# PlacaDeDezvoltareGenerala.net
KiCad netlist of a schematic drawn in Altium Designer
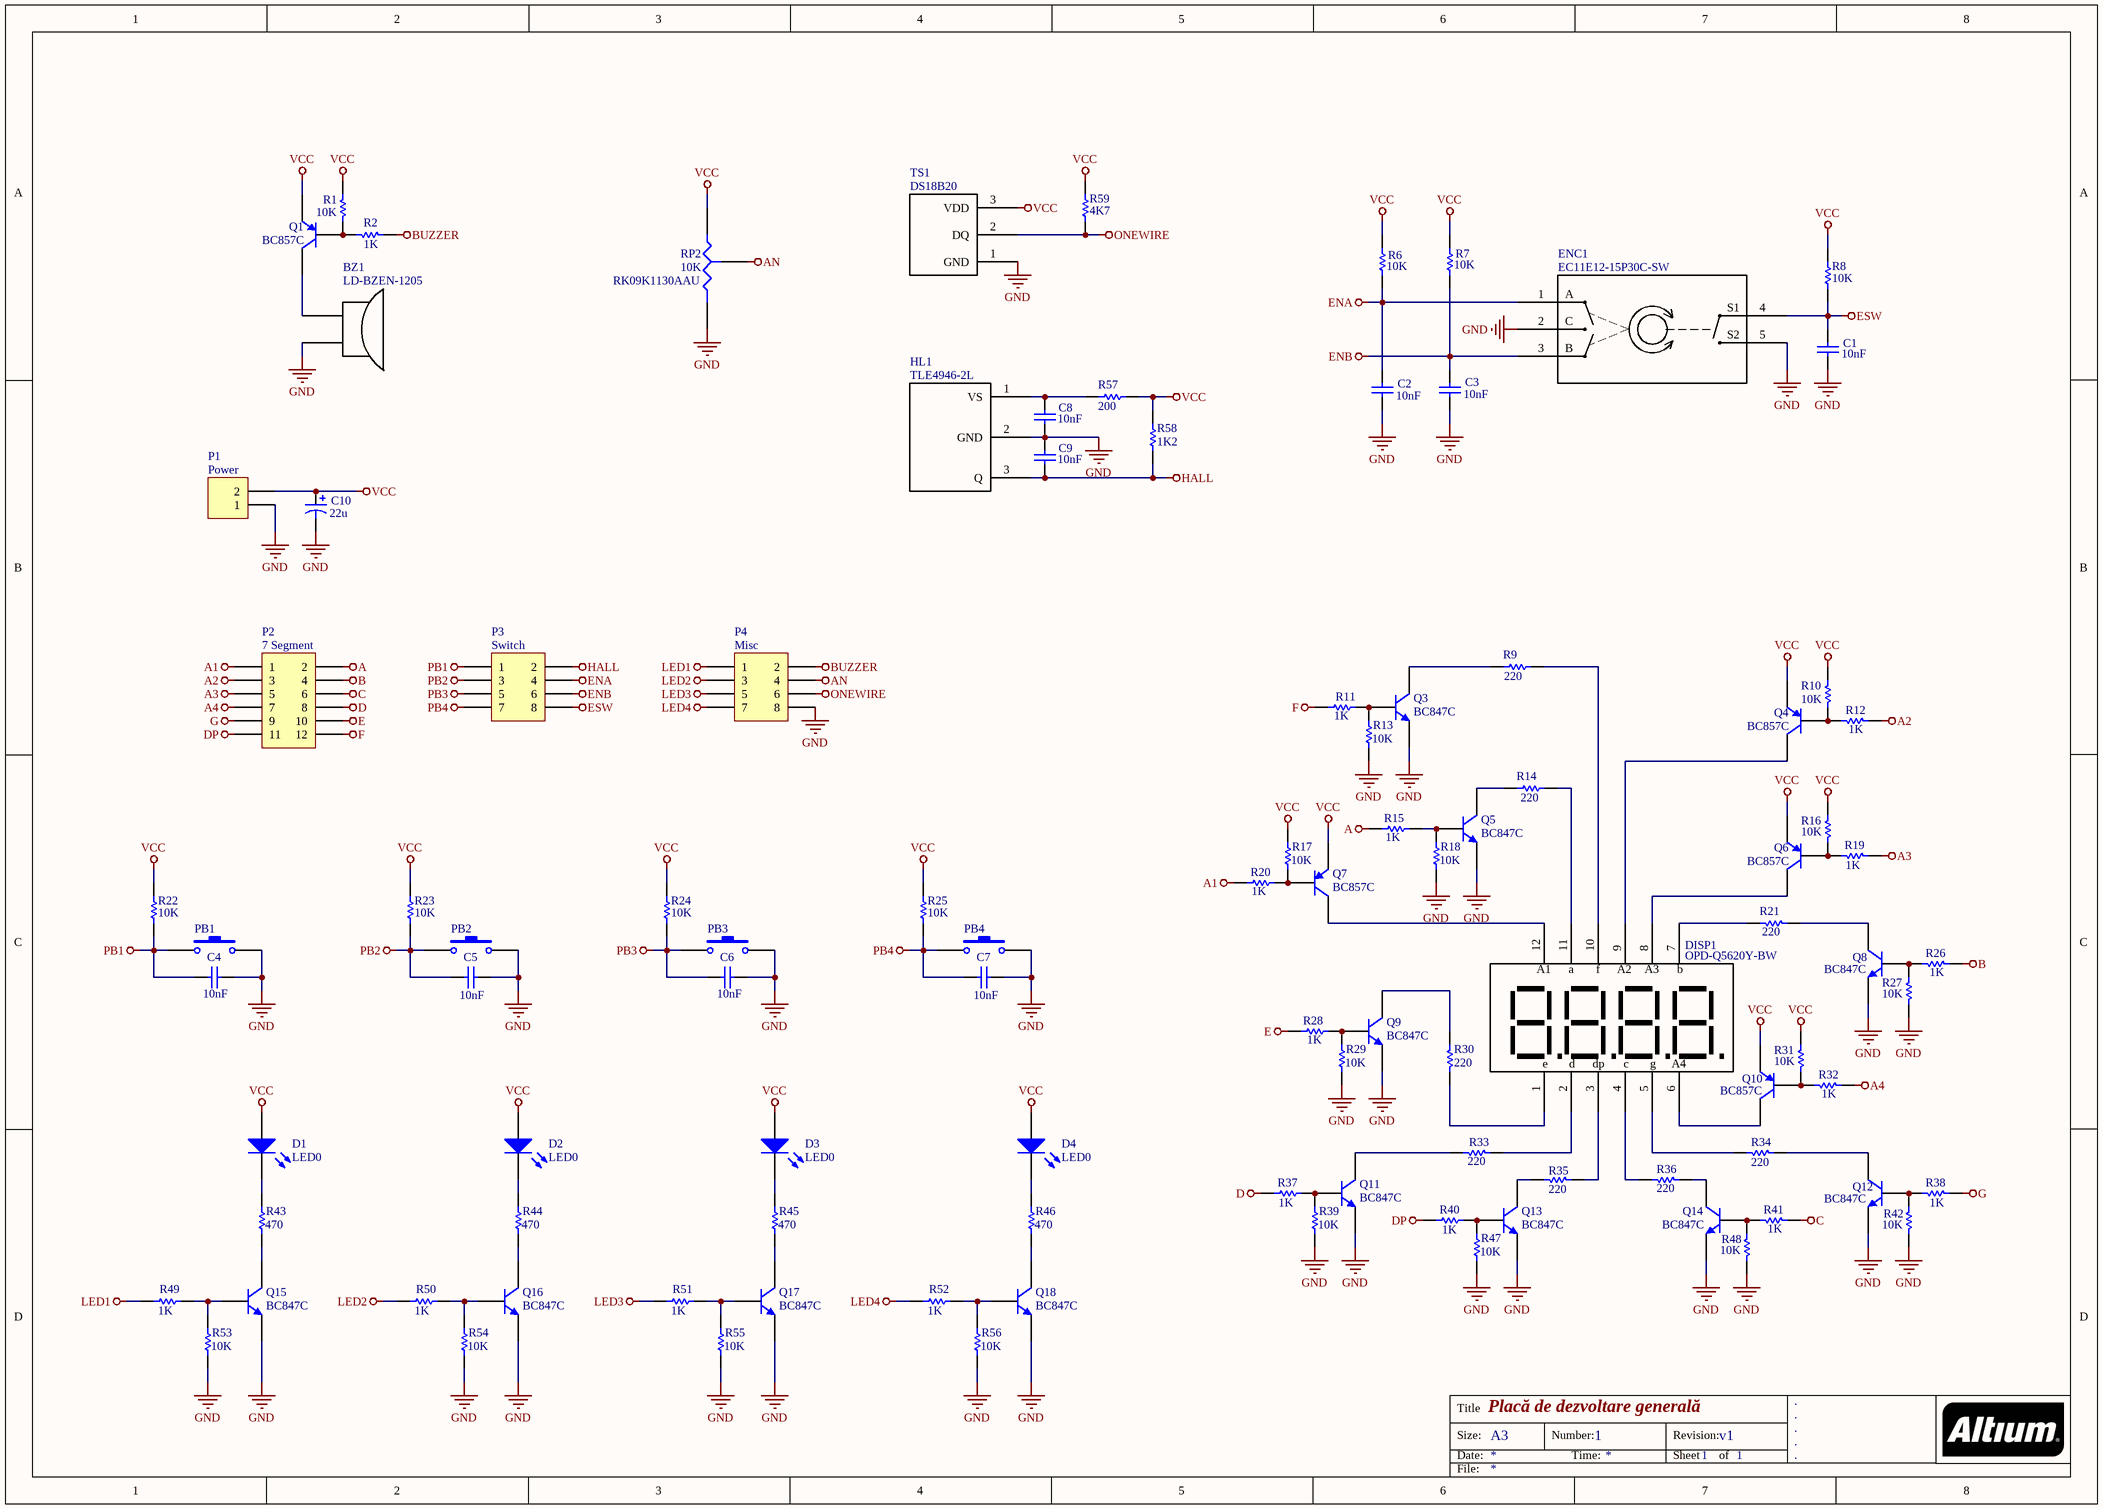
[diagram p0: PlacaDeDezvoltareGenerala.SchDoc]

(export (version "E")
  (design (tool "Eeschema 10.0.6"))
  (components
    (comp (ref "BZ1")
      (value "LD-BZEN-1205")
      (footprint "BUZZER_12.0X8.5MM")
      (libsource (lib "PlacaDeDezvoltareGenerala") (part "Buzzer"))
    )
    (comp (ref "C1")
      (value "10nF")
      (footprint "CAP 0805")
      (description "Capacitor")
      (fields (field (name "Comment") "Cap") (field (name "PUBLISHER") "Altium Limited"))
      (libsource (lib "Miscellaneous Devices") (part "Cap"))
    )
    (comp (ref "C2")
      (value "10nF")
      (footprint "CAP 0805")
      (description "Capacitor")
      (fields (field (name "Comment") "Cap") (field (name "PUBLISHER") "Altium Limited"))
      (libsource (lib "Miscellaneous Devices") (part "Cap"))
    )
    (comp (ref "C3")
      (value "10nF")
      (footprint "CAP 0805")
      (description "Capacitor")
      (fields (field (name "Comment") "Cap") (field (name "PUBLISHER") "Altium Limited"))
      (libsource (lib "Miscellaneous Devices") (part "Cap"))
    )
    (comp (ref "C4")
      (value "10nF")
      (footprint "CAP 0805")
      (description "Capacitor")
      (fields (field (name "Comment") "Cap") (field (name "PUBLISHER") "Altium Limited"))
      (libsource (lib "Miscellaneous Devices") (part "Cap"))
    )
    (comp (ref "C5")
      (value "10nF")
      (footprint "CAP 0805")
      (description "Capacitor")
      (fields (field (name "Comment") "Cap") (field (name "PUBLISHER") "Altium Limited"))
      (libsource (lib "Miscellaneous Devices") (part "Cap"))
    )
    (comp (ref "C6")
      (value "10nF")
      (footprint "CAP 0805")
      (description "Capacitor")
      (fields (field (name "Comment") "Cap") (field (name "PUBLISHER") "Altium Limited"))
      (libsource (lib "Miscellaneous Devices") (part "Cap"))
    )
    (comp (ref "C7")
      (value "10nF")
      (footprint "CAP 0805")
      (description "Capacitor")
      (fields (field (name "Comment") "Cap") (field (name "PUBLISHER") "Altium Limited"))
      (libsource (lib "Miscellaneous Devices") (part "Cap"))
    )
    (comp (ref "C8")
      (value "10nF")
      (footprint "CAP 0805")
      (description "Capacitor")
      (fields (field (name "Comment") "Cap") (field (name "PUBLISHER") "Altium Limited"))
      (libsource (lib "Miscellaneous Devices") (part "Cap"))
    )
    (comp (ref "C9")
      (value "10nF")
      (footprint "CAP 0805")
      (description "Capacitor")
      (fields (field (name "Comment") "Cap") (field (name "PUBLISHER") "Altium Limited"))
      (libsource (lib "Miscellaneous Devices") (part "Cap"))
    )
    (comp (ref "C10")
      (value "22u")
      (footprint "CAP_ELEC_6.3x4.2")
      (description "Polarized Capacitor (Radial)")
      (fields (field (name "Comment") "Cap Pol1") (field (name "PUBLISHER") "Altium Limited"))
      (libsource (lib "Miscellaneous Devices") (part "Cap Pol1"))
    )
    (comp (ref "D1")
      (value "LED0")
      (footprint "LED0603GR")
      (description "Typical INFRARED GaAs LED")
      (fields (field (name "PUBLISHER") "Altium Limited"))
      (libsource (lib "Miscellaneous Devices") (part "LED0"))
    )
    (comp (ref "D2")
      (value "LED0")
      (footprint "LED0603GR")
      (description "Typical INFRARED GaAs LED")
      (fields (field (name "PUBLISHER") "Altium Limited"))
      (libsource (lib "Miscellaneous Devices") (part "LED0"))
    )
    (comp (ref "D3")
      (value "LED0")
      (footprint "LED0603GR")
      (description "Typical INFRARED GaAs LED")
      (fields (field (name "PUBLISHER") "Altium Limited"))
      (libsource (lib "Miscellaneous Devices") (part "LED0"))
    )
    (comp (ref "D4")
      (value "LED0")
      (footprint "LED0603GR")
      (description "Typical INFRARED GaAs LED")
      (fields (field (name "PUBLISHER") "Altium Limited"))
      (libsource (lib "Miscellaneous Devices") (part "LED0"))
    )
    (comp (ref "DISP1")
      (value "OPD-Q5620Y-BW")
      (footprint "7-SEG")
      (libsource (lib "PlacaDeDezvoltareGenerala") (part "7 Segment"))
    )
    (comp (ref "ENC1")
      (value "EC11E12-15P30C-SW")
      (footprint "EC11E12")
      (libsource (lib "PlacaDeDezvoltareGenerala") (part "Encoder"))
    )
    (comp (ref "HL1")
      (value "TLE4946-2L")
      (footprint "TLE4946-2L")
      (libsource (lib "PlacaDeDezvoltareGenerala") (part "Hall Latch TLE4946-2L"))
    )
    (comp (ref "P1")
      (value "Power")
      (footprint "HEADER_1x2_2.54")
      (description "Header, 2-Pin")
      (fields (field (name "PUBLISHER") "Altium Limited"))
      (libsource (lib "Miscellaneous Connectors") (part "Header 2"))
    )
    (comp (ref "P2")
      (value "7 Segment")
      (footprint "HEADER_2x6_2.54")
      (description "Header, 6-Pin, Dual row")
      (fields (field (name "PUBLISHER") "Altium Limited"))
      (libsource (lib "Miscellaneous Connectors") (part "Header 6X2"))
    )
    (comp (ref "P3")
      (value "Switch")
      (footprint "HEADER_2x4_2.54")
      (description "Header, 4-Pin, Dual row, Right Angle")
      (fields (field (name "PUBLISHER") "Altium Limited"))
      (libsource (lib "Miscellaneous Connectors") (part "Header 4X2H"))
    )
    (comp (ref "P4")
      (value "Misc")
      (footprint "HEADER_2x4_2.54")
      (description "Header, 4-Pin, Dual row, Right Angle")
      (fields (field (name "PUBLISHER") "Altium Limited"))
      (libsource (lib "Miscellaneous Connectors") (part "Header 4X2H"))
    )
    (comp (ref "PB1")
      (value "SW-PB")
      (footprint "PUSH BUTTON")
      (description "Switch")
      (fields (field (name "PUBLISHER") "Altium Limited"))
      (libsource (lib "Miscellaneous Devices") (part "SW-PB"))
    )
    (comp (ref "PB2")
      (value "SW-PB")
      (footprint "PUSH BUTTON")
      (description "Switch")
      (fields (field (name "PUBLISHER") "Altium Limited"))
      (libsource (lib "Miscellaneous Devices") (part "SW-PB"))
    )
    (comp (ref "PB3")
      (value "SW-PB")
      (footprint "PUSH BUTTON")
      (description "Switch")
      (fields (field (name "PUBLISHER") "Altium Limited"))
      (libsource (lib "Miscellaneous Devices") (part "SW-PB"))
    )
    (comp (ref "PB4")
      (value "SW-PB")
      (footprint "PUSH BUTTON")
      (description "Switch")
      (fields (field (name "PUBLISHER") "Altium Limited"))
      (libsource (lib "Miscellaneous Devices") (part "SW-PB"))
    )
    (comp (ref "Q1")
      (value "BC857C")
      (footprint "BC847C/BC857C")
      (description "PNP General Purpose Amplifier")
      (fields (field (name "PUBLISHER") "Altium Limited"))
      (libsource (lib "Miscellaneous Devices") (part "2N3906"))
    )
    (comp (ref "Q3")
      (value "BC847C")
      (footprint "BC847C/BC857C")
      (description "NPN General Purpose Amplifier")
      (fields (field (name "PUBLISHER") "Altium Limited"))
      (libsource (lib "Miscellaneous Devices") (part "2N3904"))
    )
    (comp (ref "Q4")
      (value "BC857C")
      (footprint "BC847C/BC857C")
      (description "PNP General Purpose Amplifier")
      (fields (field (name "PUBLISHER") "Altium Limited"))
      (libsource (lib "Miscellaneous Devices") (part "2N3906"))
    )
    (comp (ref "Q5")
      (value "BC847C")
      (footprint "BC847C/BC857C")
      (description "NPN General Purpose Amplifier")
      (fields (field (name "PUBLISHER") "Altium Limited"))
      (libsource (lib "Miscellaneous Devices") (part "2N3904"))
    )
    (comp (ref "Q6")
      (value "BC857C")
      (footprint "BC847C/BC857C")
      (description "PNP General Purpose Amplifier")
      (fields (field (name "PUBLISHER") "Altium Limited"))
      (libsource (lib "Miscellaneous Devices") (part "2N3906"))
    )
    (comp (ref "Q7")
      (value "BC857C")
      (footprint "BC847C/BC857C")
      (description "PNP General Purpose Amplifier")
      (fields (field (name "PUBLISHER") "Altium Limited"))
      (libsource (lib "Miscellaneous Devices") (part "2N3906"))
    )
    (comp (ref "Q8")
      (value "BC847C")
      (footprint "BC847C/BC857C")
      (description "NPN General Purpose Amplifier")
      (fields (field (name "PUBLISHER") "Altium Limited"))
      (libsource (lib "Miscellaneous Devices") (part "2N3904"))
    )
    (comp (ref "Q9")
      (value "BC847C")
      (footprint "BC847C/BC857C")
      (description "NPN General Purpose Amplifier")
      (fields (field (name "PUBLISHER") "Altium Limited"))
      (libsource (lib "Miscellaneous Devices") (part "2N3904"))
    )
    (comp (ref "Q10")
      (value "BC857C")
      (footprint "BC847C/BC857C")
      (description "PNP General Purpose Amplifier")
      (fields (field (name "PUBLISHER") "Altium Limited"))
      (libsource (lib "Miscellaneous Devices") (part "2N3906"))
    )
    (comp (ref "Q11")
      (value "BC847C")
      (footprint "BC847C/BC857C")
      (description "NPN General Purpose Amplifier")
      (fields (field (name "PUBLISHER") "Altium Limited"))
      (libsource (lib "Miscellaneous Devices") (part "2N3904"))
    )
    (comp (ref "Q12")
      (value "BC847C")
      (footprint "BC847C/BC857C")
      (description "NPN General Purpose Amplifier")
      (fields (field (name "PUBLISHER") "Altium Limited"))
      (libsource (lib "Miscellaneous Devices") (part "2N3904"))
    )
    (comp (ref "Q13")
      (value "BC847C")
      (footprint "BC847C/BC857C")
      (description "NPN General Purpose Amplifier")
      (fields (field (name "PUBLISHER") "Altium Limited"))
      (libsource (lib "Miscellaneous Devices") (part "2N3904"))
    )
    (comp (ref "Q14")
      (value "BC847C")
      (footprint "BC847C/BC857C")
      (description "NPN General Purpose Amplifier")
      (fields (field (name "PUBLISHER") "Altium Limited"))
      (libsource (lib "Miscellaneous Devices") (part "2N3904"))
    )
    (comp (ref "Q15")
      (value "BC847C")
      (footprint "BC847C/BC857C")
      (description "NPN General Purpose Amplifier")
      (fields (field (name "PUBLISHER") "Altium Limited"))
      (libsource (lib "Miscellaneous Devices") (part "2N3904"))
    )
    (comp (ref "Q16")
      (value "BC847C")
      (footprint "BC847C/BC857C")
      (description "NPN General Purpose Amplifier")
      (fields (field (name "PUBLISHER") "Altium Limited"))
      (libsource (lib "Miscellaneous Devices") (part "2N3904"))
    )
    (comp (ref "Q17")
      (value "BC847C")
      (footprint "BC847C/BC857C")
      (description "NPN General Purpose Amplifier")
      (fields (field (name "PUBLISHER") "Altium Limited"))
      (libsource (lib "Miscellaneous Devices") (part "2N3904"))
    )
    (comp (ref "Q18")
      (value "BC847C")
      (footprint "BC847C/BC857C")
      (description "NPN General Purpose Amplifier")
      (fields (field (name "PUBLISHER") "Altium Limited"))
      (libsource (lib "Miscellaneous Devices") (part "2N3904"))
    )
    (comp (ref "R1")
      (value "10K")
      (footprint "RES 0805")
      (description "Resistor")
      (fields (field (name "Comment") "Res1") (field (name "PUBLISHER") "Altium Limited"))
      (libsource (lib "Miscellaneous Devices") (part "Res1"))
    )
    (comp (ref "R2")
      (value "1K")
      (footprint "RES 0805")
      (description "Resistor")
      (fields (field (name "Comment") "Res1") (field (name "PUBLISHER") "Altium Limited"))
      (libsource (lib "Miscellaneous Devices") (part "Res1"))
    )
    (comp (ref "R6")
      (value "10K")
      (footprint "RES 0805")
      (description "Resistor")
      (fields (field (name "Comment") "Res1") (field (name "PUBLISHER") "Altium Limited"))
      (libsource (lib "Miscellaneous Devices") (part "Res1"))
    )
    (comp (ref "R7")
      (value "10K")
      (footprint "RES 0805")
      (description "Resistor")
      (fields (field (name "Comment") "Res1") (field (name "PUBLISHER") "Altium Limited"))
      (libsource (lib "Miscellaneous Devices") (part "Res1"))
    )
    (comp (ref "R8")
      (value "10K")
      (footprint "RES 0805")
      (description "Resistor")
      (fields (field (name "Comment") "Res1") (field (name "PUBLISHER") "Altium Limited"))
      (libsource (lib "Miscellaneous Devices") (part "Res1"))
    )
    (comp (ref "R9")
      (value "220")
      (footprint "RES 0805")
      (description "Resistor")
      (fields (field (name "Comment") "Res1") (field (name "PUBLISHER") "Altium Limited"))
      (libsource (lib "Miscellaneous Devices") (part "Res1"))
    )
    (comp (ref "R10")
      (value "10K")
      (footprint "RES 0805")
      (description "Resistor")
      (fields (field (name "Comment") "Res1") (field (name "PUBLISHER") "Altium Limited"))
      (libsource (lib "Miscellaneous Devices") (part "Res1"))
    )
    (comp (ref "R11")
      (value "1K")
      (footprint "RES 0805")
      (description "Resistor")
      (fields (field (name "Comment") "Res1") (field (name "PUBLISHER") "Altium Limited"))
      (libsource (lib "Miscellaneous Devices") (part "Res1"))
    )
    (comp (ref "R12")
      (value "1K")
      (footprint "RES 0805")
      (description "Resistor")
      (fields (field (name "Comment") "Res1") (field (name "PUBLISHER") "Altium Limited"))
      (libsource (lib "Miscellaneous Devices") (part "Res1"))
    )
    (comp (ref "R13")
      (value "10K")
      (footprint "RES 0805")
      (description "Resistor")
      (fields (field (name "Comment") "Res1") (field (name "PUBLISHER") "Altium Limited"))
      (libsource (lib "Miscellaneous Devices") (part "Res1"))
    )
    (comp (ref "R14")
      (value "220")
      (footprint "RES 0805")
      (description "Resistor")
      (fields (field (name "Comment") "Res1") (field (name "PUBLISHER") "Altium Limited"))
      (libsource (lib "Miscellaneous Devices") (part "Res1"))
    )
    (comp (ref "R15")
      (value "1K")
      (footprint "RES 0805")
      (description "Resistor")
      (fields (field (name "Comment") "Res1") (field (name "PUBLISHER") "Altium Limited"))
      (libsource (lib "Miscellaneous Devices") (part "Res1"))
    )
    (comp (ref "R16")
      (value "10K")
      (footprint "RES 0805")
      (description "Resistor")
      (fields (field (name "Comment") "Res1") (field (name "PUBLISHER") "Altium Limited"))
      (libsource (lib "Miscellaneous Devices") (part "Res1"))
    )
    (comp (ref "R17")
      (value "10K")
      (footprint "RES 0805")
      (description "Resistor")
      (fields (field (name "Comment") "Res1") (field (name "PUBLISHER") "Altium Limited"))
      (libsource (lib "Miscellaneous Devices") (part "Res1"))
    )
    (comp (ref "R18")
      (value "10K")
      (footprint "RES 0805")
      (description "Resistor")
      (fields (field (name "Comment") "Res1") (field (name "PUBLISHER") "Altium Limited"))
      (libsource (lib "Miscellaneous Devices") (part "Res1"))
    )
    (comp (ref "R19")
      (value "1K")
      (footprint "RES 0805")
      (description "Resistor")
      (fields (field (name "Comment") "Res1") (field (name "PUBLISHER") "Altium Limited"))
      (libsource (lib "Miscellaneous Devices") (part "Res1"))
    )
    (comp (ref "R20")
      (value "1K")
      (footprint "RES 0805")
      (description "Resistor")
      (fields (field (name "Comment") "Res1") (field (name "PUBLISHER") "Altium Limited"))
      (libsource (lib "Miscellaneous Devices") (part "Res1"))
    )
    (comp (ref "R21")
      (value "220")
      (footprint "RES 0805")
      (description "Resistor")
      (fields (field (name "Comment") "Res1") (field (name "PUBLISHER") "Altium Limited"))
      (libsource (lib "Miscellaneous Devices") (part "Res1"))
    )
    (comp (ref "R22")
      (value "10K")
      (footprint "RES 0805")
      (description "Resistor")
      (fields (field (name "Comment") "Res1") (field (name "PUBLISHER") "Altium Limited"))
      (libsource (lib "Miscellaneous Devices") (part "Res1"))
    )
    (comp (ref "R23")
      (value "10K")
      (footprint "RES 0805")
      (description "Resistor")
      (fields (field (name "Comment") "Res1") (field (name "PUBLISHER") "Altium Limited"))
      (libsource (lib "Miscellaneous Devices") (part "Res1"))
    )
    (comp (ref "R24")
      (value "10K")
      (footprint "RES 0805")
      (description "Resistor")
      (fields (field (name "Comment") "Res1") (field (name "PUBLISHER") "Altium Limited"))
      (libsource (lib "Miscellaneous Devices") (part "Res1"))
    )
    (comp (ref "R25")
      (value "10K")
      (footprint "RES 0805")
      (description "Resistor")
      (fields (field (name "Comment") "Res1") (field (name "PUBLISHER") "Altium Limited"))
      (libsource (lib "Miscellaneous Devices") (part "Res1"))
    )
    (comp (ref "R26")
      (value "1K")
      (footprint "RES 0805")
      (description "Resistor")
      (fields (field (name "Comment") "Res1") (field (name "PUBLISHER") "Altium Limited"))
      (libsource (lib "Miscellaneous Devices") (part "Res1"))
    )
    (comp (ref "R27")
      (value "10K")
      (footprint "RES 0805")
      (description "Resistor")
      (fields (field (name "Comment") "Res1") (field (name "PUBLISHER") "Altium Limited"))
      (libsource (lib "Miscellaneous Devices") (part "Res1"))
    )
    (comp (ref "R28")
      (value "1K")
      (footprint "RES 0805")
      (description "Resistor")
      (fields (field (name "Comment") "Res1") (field (name "PUBLISHER") "Altium Limited"))
      (libsource (lib "Miscellaneous Devices") (part "Res1"))
    )
    (comp (ref "R29")
      (value "10K")
      (footprint "RES 0805")
      (description "Resistor")
      (fields (field (name "Comment") "Res1") (field (name "PUBLISHER") "Altium Limited"))
      (libsource (lib "Miscellaneous Devices") (part "Res1"))
    )
    (comp (ref "R30")
      (value "220")
      (footprint "RES 0805")
      (description "Resistor")
      (fields (field (name "Comment") "Res1") (field (name "PUBLISHER") "Altium Limited"))
      (libsource (lib "Miscellaneous Devices") (part "Res1"))
    )
    (comp (ref "R31")
      (value "10K")
      (footprint "RES 0805")
      (description "Resistor")
      (fields (field (name "Comment") "Res1") (field (name "PUBLISHER") "Altium Limited"))
      (libsource (lib "Miscellaneous Devices") (part "Res1"))
    )
    (comp (ref "R32")
      (value "1K")
      (footprint "RES 0805")
      (description "Resistor")
      (fields (field (name "Comment") "Res1") (field (name "PUBLISHER") "Altium Limited"))
      (libsource (lib "Miscellaneous Devices") (part "Res1"))
    )
    (comp (ref "R33")
      (value "220")
      (footprint "RES 0805")
      (description "Resistor")
      (fields (field (name "Comment") "Res1") (field (name "PUBLISHER") "Altium Limited"))
      (libsource (lib "Miscellaneous Devices") (part "Res1"))
    )
    (comp (ref "R34")
      (value "220")
      (footprint "RES 0805")
      (description "Resistor")
      (fields (field (name "Comment") "Res1") (field (name "PUBLISHER") "Altium Limited"))
      (libsource (lib "Miscellaneous Devices") (part "Res1"))
    )
    (comp (ref "R35")
      (value "220")
      (footprint "RES 0805")
      (description "Resistor")
      (fields (field (name "Comment") "Res1") (field (name "PUBLISHER") "Altium Limited"))
      (libsource (lib "Miscellaneous Devices") (part "Res1"))
    )
    (comp (ref "R36")
      (value "220")
      (footprint "RES 0805")
      (description "Resistor")
      (fields (field (name "Comment") "Res1") (field (name "PUBLISHER") "Altium Limited"))
      (libsource (lib "Miscellaneous Devices") (part "Res1"))
    )
    (comp (ref "R37")
      (value "1K")
      (footprint "RES 0805")
      (description "Resistor")
      (fields (field (name "Comment") "Res1") (field (name "PUBLISHER") "Altium Limited"))
      (libsource (lib "Miscellaneous Devices") (part "Res1"))
    )
    (comp (ref "R38")
      (value "1K")
      (footprint "RES 0805")
      (description "Resistor")
      (fields (field (name "Comment") "Res1") (field (name "PUBLISHER") "Altium Limited"))
      (libsource (lib "Miscellaneous Devices") (part "Res1"))
    )
    (comp (ref "R39")
      (value "10K")
      (footprint "RES 0805")
      (description "Resistor")
      (fields (field (name "Comment") "Res1") (field (name "PUBLISHER") "Altium Limited"))
      (libsource (lib "Miscellaneous Devices") (part "Res1"))
    )
    (comp (ref "R40")
      (value "1K")
      (footprint "RES 0805")
      (description "Resistor")
      (fields (field (name "Comment") "Res1") (field (name "PUBLISHER") "Altium Limited"))
      (libsource (lib "Miscellaneous Devices") (part "Res1"))
    )
    (comp (ref "R41")
      (value "1K")
      (footprint "RES 0805")
      (description "Resistor")
      (fields (field (name "Comment") "Res1") (field (name "PUBLISHER") "Altium Limited"))
      (libsource (lib "Miscellaneous Devices") (part "Res1"))
    )
    (comp (ref "R42")
      (value "10K")
      (footprint "RES 0805")
      (description "Resistor")
      (fields (field (name "Comment") "Res1") (field (name "PUBLISHER") "Altium Limited"))
      (libsource (lib "Miscellaneous Devices") (part "Res1"))
    )
    (comp (ref "R43")
      (value "470")
      (footprint "RES 0805")
      (description "Resistor")
      (fields (field (name "Comment") "Res1") (field (name "PUBLISHER") "Altium Limited"))
      (libsource (lib "Miscellaneous Devices") (part "Res1"))
    )
    (comp (ref "R44")
      (value "470")
      (footprint "RES 0805")
      (description "Resistor")
      (fields (field (name "Comment") "Res1") (field (name "PUBLISHER") "Altium Limited"))
      (libsource (lib "Miscellaneous Devices") (part "Res1"))
    )
    (comp (ref "R45")
      (value "470")
      (footprint "RES 0805")
      (description "Resistor")
      (fields (field (name "Comment") "Res1") (field (name "PUBLISHER") "Altium Limited"))
      (libsource (lib "Miscellaneous Devices") (part "Res1"))
    )
    (comp (ref "R46")
      (value "470")
      (footprint "RES 0805")
      (description "Resistor")
      (fields (field (name "Comment") "Res1") (field (name "PUBLISHER") "Altium Limited"))
      (libsource (lib "Miscellaneous Devices") (part "Res1"))
    )
    (comp (ref "R47")
      (value "10K")
      (footprint "RES 0805")
      (description "Resistor")
      (fields (field (name "Comment") "Res1") (field (name "PUBLISHER") "Altium Limited"))
      (libsource (lib "Miscellaneous Devices") (part "Res1"))
    )
    (comp (ref "R48")
      (value "10K")
      (footprint "RES 0805")
      (description "Resistor")
      (fields (field (name "Comment") "Res1") (field (name "PUBLISHER") "Altium Limited"))
      (libsource (lib "Miscellaneous Devices") (part "Res1"))
    )
    (comp (ref "R49")
      (value "1K")
      (footprint "RES 0805")
      (description "Resistor")
      (fields (field (name "Comment") "Res1") (field (name "PUBLISHER") "Altium Limited"))
      (libsource (lib "Miscellaneous Devices") (part "Res1"))
    )
    (comp (ref "R50")
      (value "1K")
      (footprint "RES 0805")
      (description "Resistor")
      (fields (field (name "Comment") "Res1") (field (name "PUBLISHER") "Altium Limited"))
      (libsource (lib "Miscellaneous Devices") (part "Res1"))
    )
    (comp (ref "R51")
      (value "1K")
      (footprint "RES 0805")
      (description "Resistor")
      (fields (field (name "Comment") "Res1") (field (name "PUBLISHER") "Altium Limited"))
      (libsource (lib "Miscellaneous Devices") (part "Res1"))
    )
    (comp (ref "R52")
      (value "1K")
      (footprint "RES 0805")
      (description "Resistor")
      (fields (field (name "Comment") "Res1") (field (name "PUBLISHER") "Altium Limited"))
      (libsource (lib "Miscellaneous Devices") (part "Res1"))
    )
    (comp (ref "R53")
      (value "10K")
      (footprint "RES 0805")
      (description "Resistor")
      (fields (field (name "Comment") "Res1") (field (name "PUBLISHER") "Altium Limited"))
      (libsource (lib "Miscellaneous Devices") (part "Res1"))
    )
    (comp (ref "R54")
      (value "10K")
      (footprint "RES 0805")
      (description "Resistor")
      (fields (field (name "Comment") "Res1") (field (name "PUBLISHER") "Altium Limited"))
      (libsource (lib "Miscellaneous Devices") (part "Res1"))
    )
    (comp (ref "R55")
      (value "10K")
      (footprint "RES 0805")
      (description "Resistor")
      (fields (field (name "Comment") "Res1") (field (name "PUBLISHER") "Altium Limited"))
      (libsource (lib "Miscellaneous Devices") (part "Res1"))
    )
    (comp (ref "R56")
      (value "10K")
      (footprint "RES 0805")
      (description "Resistor")
      (fields (field (name "Comment") "Res1") (field (name "PUBLISHER") "Altium Limited"))
      (libsource (lib "Miscellaneous Devices") (part "Res1"))
    )
    (comp (ref "R57")
      (value "200")
      (footprint "RES 0805")
      (description "Resistor")
      (fields (field (name "Comment") "Res1") (field (name "PUBLISHER") "Altium Limited"))
      (libsource (lib "Miscellaneous Devices") (part "Res1"))
    )
    (comp (ref "R58")
      (value "1K2")
      (footprint "RES 0805")
      (description "Resistor")
      (fields (field (name "Comment") "Res1") (field (name "PUBLISHER") "Altium Limited"))
      (libsource (lib "Miscellaneous Devices") (part "Res1"))
    )
    (comp (ref "R59")
      (value "4K7")
      (footprint "RES 0805")
      (description "Resistor")
      (fields (field (name "Comment") "Res1") (field (name "PUBLISHER") "Altium Limited"))
      (libsource (lib "Miscellaneous Devices") (part "Res1"))
    )
    (comp (ref "RP2")
      (value "RK09K1130AAU")
      (footprint "RK09K1130AAU")
      (description "Tapped Resistor")
      (fields (field (name "ALTIUM_VALUE") "10K") (field (name "PUBLISHER") "Altium Limited"))
      (libsource (lib "Miscellaneous Devices") (part "Res Tap"))
    )
    (comp (ref "TS1")
      (value "DS18B20")
      (footprint "DS18B20")
      (libsource (lib "PlacaDeDezvoltareGenerala") (part "DS18B20"))
    )
  )
  (nets
    (net (code "1") (name "A") (class "Default")
      (node (ref "P2") (pin "2") (pinfunction "2_2") (pintype "passive"))
      (node (ref "R15") (pin "2") (pinfunction "2_2") (pintype "passive"))
    )
    (net (code "2") (name "A1") (class "Default")
      (node (ref "P2") (pin "1") (pinfunction "1_1") (pintype "passive"))
      (node (ref "R20") (pin "2") (pinfunction "2_2") (pintype "passive"))
    )
    (net (code "3") (name "A2") (class "Default")
      (node (ref "P2") (pin "3") (pinfunction "3_3") (pintype "passive"))
      (node (ref "R12") (pin "2") (pinfunction "2_2") (pintype "passive"))
    )
    (net (code "4") (name "A3") (class "Default")
      (node (ref "P2") (pin "5") (pinfunction "5_5") (pintype "passive"))
      (node (ref "R19") (pin "2") (pinfunction "2_2") (pintype "passive"))
    )
    (net (code "5") (name "A4") (class "Default")
      (node (ref "P2") (pin "7") (pinfunction "7_7") (pintype "passive"))
      (node (ref "R32") (pin "2") (pinfunction "2_2") (pintype "passive"))
    )
    (net (code "6") (name "AN") (class "Default")
      (node (ref "P4") (pin "4") (pinfunction "4_4") (pintype "passive"))
      (node (ref "RP2") (pin "3") (pinfunction "TAP_3") (pintype "passive"))
    )
    (net (code "7") (name "B") (class "Default")
      (node (ref "P2") (pin "4") (pinfunction "4_4") (pintype "passive"))
      (node (ref "R26") (pin "2") (pinfunction "2_2") (pintype "passive"))
    )
    (net (code "8") (name "BUZZER") (class "Default")
      (node (ref "P4") (pin "2") (pinfunction "2_2") (pintype "passive"))
      (node (ref "R2") (pin "2") (pinfunction "2_2") (pintype "passive"))
    )
    (net (code "9") (name "C") (class "Default")
      (node (ref "P2") (pin "6") (pinfunction "6_6") (pintype "passive"))
      (node (ref "R41") (pin "2") (pinfunction "2_2") (pintype "passive"))
    )
    (net (code "10") (name "D") (class "Default")
      (node (ref "P2") (pin "8") (pinfunction "8_8") (pintype "passive"))
      (node (ref "R37") (pin "2") (pinfunction "2_2") (pintype "passive"))
    )
    (net (code "11") (name "DP") (class "Default")
      (node (ref "P2") (pin "11") (pinfunction "11_11") (pintype "passive"))
      (node (ref "R40") (pin "2") (pinfunction "2_2") (pintype "passive"))
    )
    (net (code "12") (name "E") (class "Default")
      (node (ref "P2") (pin "10") (pinfunction "10_10") (pintype "passive"))
      (node (ref "R28") (pin "2") (pinfunction "2_2") (pintype "passive"))
    )
    (net (code "13") (name "ENA") (class "Default")
      (node (ref "C2") (pin "2") (pinfunction "2_2") (pintype "passive"))
      (node (ref "ENC1") (pin "1") (pinfunction "2_1") (pintype "passive"))
      (node (ref "P3") (pin "4") (pinfunction "4_4") (pintype "passive"))
      (node (ref "R6") (pin "1") (pinfunction "1_1") (pintype "passive"))
    )
    (net (code "14") (name "ENB") (class "Default")
      (node (ref "C3") (pin "2") (pinfunction "2_2") (pintype "passive"))
      (node (ref "ENC1") (pin "3") (pinfunction "4_3") (pintype "passive"))
      (node (ref "P3") (pin "6") (pinfunction "6_6") (pintype "passive"))
      (node (ref "R7") (pin "1") (pinfunction "1_1") (pintype "passive"))
    )
    (net (code "15") (name "ESW") (class "Default")
      (node (ref "C1") (pin "2") (pinfunction "2_2") (pintype "passive"))
      (node (ref "ENC1") (pin "4") (pinfunction "5_4") (pintype "passive"))
      (node (ref "P3") (pin "8") (pinfunction "8_8") (pintype "passive"))
      (node (ref "R8") (pin "1") (pinfunction "1_1") (pintype "passive"))
    )
    (net (code "16") (name "F") (class "Default")
      (node (ref "P2") (pin "12") (pinfunction "12_12") (pintype "passive"))
      (node (ref "R11") (pin "2") (pinfunction "2_2") (pintype "passive"))
    )
    (net (code "17") (name "G") (class "Default")
      (node (ref "P2") (pin "9") (pinfunction "9_9") (pintype "passive"))
      (node (ref "R38") (pin "2") (pinfunction "2_2") (pintype "passive"))
    )
    (net (code "18") (name "GND") (class "Default")
      (node (ref "BZ1") (pin "2") (pinfunction "2_2") (pintype "passive"))
      (node (ref "C1") (pin "1") (pinfunction "1_1") (pintype "passive"))
      (node (ref "C10") (pin "2") (pinfunction "2_2") (pintype "passive"))
      (node (ref "C2") (pin "1") (pinfunction "1_1") (pintype "passive"))
      (node (ref "C3") (pin "1") (pinfunction "1_1") (pintype "passive"))
      (node (ref "C4") (pin "1") (pinfunction "1_1") (pintype "passive"))
      (node (ref "C5") (pin "1") (pinfunction "1_1") (pintype "passive"))
      (node (ref "C6") (pin "1") (pinfunction "1_1") (pintype "passive"))
      (node (ref "C7") (pin "1") (pinfunction "1_1") (pintype "passive"))
      (node (ref "C8") (pin "2") (pinfunction "2_2") (pintype "passive"))
      (node (ref "C9") (pin "1") (pinfunction "1_1") (pintype "passive"))
      (node (ref "ENC1") (pin "2") (pinfunction "3_2") (pintype "passive"))
      (node (ref "ENC1") (pin "5") (pinfunction "6_5") (pintype "passive"))
      (node (ref "HL1") (pin "2") (pinfunction "GND_2") (pintype "passive"))
      (node (ref "P1") (pin "1") (pinfunction "1_1") (pintype "passive"))
      (node (ref "P4") (pin "8") (pinfunction "8_8") (pintype "passive"))
      (node (ref "PB1") (pin "2") (pinfunction "2_2") (pintype "passive"))
      (node (ref "PB2") (pin "2") (pinfunction "2_2") (pintype "passive"))
      (node (ref "PB3") (pin "2") (pinfunction "2_2") (pintype "passive"))
      (node (ref "PB4") (pin "2") (pinfunction "2_2") (pintype "passive"))
      (node (ref "Q11") (pin "1") (pinfunction "E_1") (pintype "passive"))
      (node (ref "Q12") (pin "1") (pinfunction "E_1") (pintype "passive"))
      (node (ref "Q13") (pin "1") (pinfunction "E_1") (pintype "passive"))
      (node (ref "Q14") (pin "1") (pinfunction "E_1") (pintype "passive"))
      (node (ref "Q15") (pin "1") (pinfunction "E_1") (pintype "passive"))
      (node (ref "Q16") (pin "1") (pinfunction "E_1") (pintype "passive"))
      (node (ref "Q17") (pin "1") (pinfunction "E_1") (pintype "passive"))
      (node (ref "Q18") (pin "1") (pinfunction "E_1") (pintype "passive"))
      (node (ref "Q3") (pin "1") (pinfunction "E_1") (pintype "passive"))
      (node (ref "Q5") (pin "1") (pinfunction "E_1") (pintype "passive"))
      (node (ref "Q8") (pin "1") (pinfunction "E_1") (pintype "passive"))
      (node (ref "Q9") (pin "1") (pinfunction "E_1") (pintype "passive"))
      (node (ref "R13") (pin "2") (pinfunction "2_2") (pintype "passive"))
      (node (ref "R18") (pin "2") (pinfunction "2_2") (pintype "passive"))
      (node (ref "R27") (pin "2") (pinfunction "2_2") (pintype "passive"))
      (node (ref "R29") (pin "2") (pinfunction "2_2") (pintype "passive"))
      (node (ref "R39") (pin "2") (pinfunction "2_2") (pintype "passive"))
      (node (ref "R42") (pin "2") (pinfunction "2_2") (pintype "passive"))
      (node (ref "R47") (pin "2") (pinfunction "2_2") (pintype "passive"))
      (node (ref "R48") (pin "2") (pinfunction "2_2") (pintype "passive"))
      (node (ref "R53") (pin "2") (pinfunction "2_2") (pintype "passive"))
      (node (ref "R54") (pin "2") (pinfunction "2_2") (pintype "passive"))
      (node (ref "R55") (pin "2") (pinfunction "2_2") (pintype "passive"))
      (node (ref "R56") (pin "2") (pinfunction "2_2") (pintype "passive"))
      (node (ref "RP2") (pin "2") (pinfunction "B_2") (pintype "passive"))
      (node (ref "TS1") (pin "1") (pinfunction "GND_1") (pintype "passive"))
    )
    (net (code "19") (name "HALL") (class "Default")
      (node (ref "C9") (pin "2") (pinfunction "2_2") (pintype "passive"))
      (node (ref "HL1") (pin "3") (pinfunction "Q_3") (pintype "passive"))
      (node (ref "P3") (pin "2") (pinfunction "2_2") (pintype "passive"))
      (node (ref "R58") (pin "1") (pinfunction "1_1") (pintype "passive"))
    )
    (net (code "20") (name "LED1") (class "Default")
      (node (ref "P4") (pin "1") (pinfunction "1_1") (pintype "passive"))
      (node (ref "R49") (pin "1") (pinfunction "1_1") (pintype "passive"))
    )
    (net (code "21") (name "LED2") (class "Default")
      (node (ref "P4") (pin "3") (pinfunction "3_3") (pintype "passive"))
      (node (ref "R50") (pin "1") (pinfunction "1_1") (pintype "passive"))
    )
    (net (code "22") (name "LED3") (class "Default")
      (node (ref "P4") (pin "5") (pinfunction "5_5") (pintype "passive"))
      (node (ref "R51") (pin "1") (pinfunction "1_1") (pintype "passive"))
    )
    (net (code "23") (name "LED4") (class "Default")
      (node (ref "P4") (pin "7") (pinfunction "7_7") (pintype "passive"))
      (node (ref "R52") (pin "1") (pinfunction "1_1") (pintype "passive"))
    )
    (net (code "24") (name "Net-(D1-K)") (class "Default")
      (node (ref "D1") (pin "2") (pinfunction "K_2") (pintype "passive"))
      (node (ref "R43") (pin "1") (pinfunction "1_1") (pintype "passive"))
    )
    (net (code "25") (name "Net-(D2-K)") (class "Default")
      (node (ref "D2") (pin "2") (pinfunction "K_2") (pintype "passive"))
      (node (ref "R44") (pin "1") (pinfunction "1_1") (pintype "passive"))
    )
    (net (code "26") (name "Net-(D3-K)") (class "Default")
      (node (ref "D3") (pin "2") (pinfunction "K_2") (pintype "passive"))
      (node (ref "R45") (pin "1") (pinfunction "1_1") (pintype "passive"))
    )
    (net (code "27") (name "Net-(D4-K)") (class "Default")
      (node (ref "D4") (pin "2") (pinfunction "K_2") (pintype "passive"))
      (node (ref "R46") (pin "1") (pinfunction "1_1") (pintype "passive"))
    )
    (net (code "28") (name "Net-(DISP1-7)") (class "Default")
      (node (ref "DISP1") (pin "12") (pinfunction "7_12") (pintype "passive"))
      (node (ref "Q7") (pin "3") (pinfunction "C_3") (pintype "passive"))
    )
    (net (code "29") (name "Net-(DISP1-8)") (class "Default")
      (node (ref "DISP1") (pin "11") (pinfunction "8_11") (pintype "passive"))
      (node (ref "R14") (pin "1") (pinfunction "1_1") (pintype "passive"))
    )
    (net (code "30") (name "Net-(DISP1-9)") (class "Default")
      (node (ref "DISP1") (pin "10") (pinfunction "9_10") (pintype "passive"))
      (node (ref "R9") (pin "1") (pinfunction "1_1") (pintype "passive"))
    )
    (net (code "31") (name "Net-(DISP1-10)") (class "Default")
      (node (ref "DISP1") (pin "9") (pinfunction "10_9") (pintype "passive"))
      (node (ref "Q4") (pin "3") (pinfunction "C_3") (pintype "passive"))
    )
    (net (code "32") (name "Net-(DISP1-11)") (class "Default")
      (node (ref "DISP1") (pin "8") (pinfunction "11_8") (pintype "passive"))
      (node (ref "Q6") (pin "3") (pinfunction "C_3") (pintype "passive"))
    )
    (net (code "33") (name "Net-(DISP1-12)") (class "Default")
      (node (ref "DISP1") (pin "7") (pinfunction "12_7") (pintype "passive"))
      (node (ref "R21") (pin "1") (pinfunction "1_1") (pintype "passive"))
    )
    (net (code "34") (name "Net-(DISP1-13)") (class "Default")
      (node (ref "DISP1") (pin "1") (pinfunction "13_1") (pintype "passive"))
      (node (ref "R30") (pin "1") (pinfunction "1_1") (pintype "passive"))
    )
    (net (code "35") (name "Net-(DISP1-14)") (class "Default")
      (node (ref "DISP1") (pin "2") (pinfunction "14_2") (pintype "passive"))
      (node (ref "R33") (pin "2") (pinfunction "2_2") (pintype "passive"))
    )
    (net (code "36") (name "Net-(DISP1-15)") (class "Default")
      (node (ref "DISP1") (pin "3") (pinfunction "15_3") (pintype "passive"))
      (node (ref "R35") (pin "2") (pinfunction "2_2") (pintype "passive"))
    )
    (net (code "37") (name "Net-(DISP1-16)") (class "Default")
      (node (ref "DISP1") (pin "4") (pinfunction "16_4") (pintype "passive"))
      (node (ref "R36") (pin "1") (pinfunction "1_1") (pintype "passive"))
    )
    (net (code "38") (name "Net-(DISP1-17)") (class "Default")
      (node (ref "DISP1") (pin "5") (pinfunction "17_5") (pintype "passive"))
      (node (ref "R34") (pin "1") (pinfunction "1_1") (pintype "passive"))
    )
    (net (code "39") (name "Net-(DISP1-18)") (class "Default")
      (node (ref "DISP1") (pin "6") (pinfunction "18_6") (pintype "passive"))
      (node (ref "Q10") (pin "3") (pinfunction "C_3") (pintype "passive"))
    )
    (net (code "40") (name "Net-(HL1-VS)") (class "Default")
      (node (ref "C8") (pin "1") (pinfunction "1_1") (pintype "passive"))
      (node (ref "HL1") (pin "1") (pinfunction "VS_1") (pintype "passive"))
      (node (ref "R57") (pin "1") (pinfunction "1_1") (pintype "passive"))
    )
    (net (code "41") (name "Net-(Q1-B)") (class "Default")
      (node (ref "Q1") (pin "2") (pinfunction "B_2") (pintype "passive"))
      (node (ref "R1") (pin "2") (pinfunction "2_2") (pintype "passive"))
      (node (ref "R2") (pin "1") (pinfunction "1_1") (pintype "passive"))
    )
    (net (code "42") (name "Net-(Q1-C)") (class "Default")
      (node (ref "BZ1") (pin "1") (pinfunction "1_1") (pintype "passive"))
      (node (ref "Q1") (pin "3") (pinfunction "C_3") (pintype "passive"))
    )
    (net (code "43") (name "Net-(Q3-B)") (class "Default")
      (node (ref "Q3") (pin "2") (pinfunction "B_2") (pintype "passive"))
      (node (ref "R11") (pin "1") (pinfunction "1_1") (pintype "passive"))
      (node (ref "R13") (pin "1") (pinfunction "1_1") (pintype "passive"))
    )
    (net (code "44") (name "Net-(Q3-C)") (class "Default")
      (node (ref "Q3") (pin "3") (pinfunction "C_3") (pintype "passive"))
      (node (ref "R9") (pin "2") (pinfunction "2_2") (pintype "passive"))
    )
    (net (code "45") (name "Net-(Q4-B)") (class "Default")
      (node (ref "Q4") (pin "2") (pinfunction "B_2") (pintype "passive"))
      (node (ref "R10") (pin "2") (pinfunction "2_2") (pintype "passive"))
      (node (ref "R12") (pin "1") (pinfunction "1_1") (pintype "passive"))
    )
    (net (code "46") (name "Net-(Q5-B)") (class "Default")
      (node (ref "Q5") (pin "2") (pinfunction "B_2") (pintype "passive"))
      (node (ref "R15") (pin "1") (pinfunction "1_1") (pintype "passive"))
      (node (ref "R18") (pin "1") (pinfunction "1_1") (pintype "passive"))
    )
    (net (code "47") (name "Net-(Q5-C)") (class "Default")
      (node (ref "Q5") (pin "3") (pinfunction "C_3") (pintype "passive"))
      (node (ref "R14") (pin "2") (pinfunction "2_2") (pintype "passive"))
    )
    (net (code "48") (name "Net-(Q6-B)") (class "Default")
      (node (ref "Q6") (pin "2") (pinfunction "B_2") (pintype "passive"))
      (node (ref "R16") (pin "2") (pinfunction "2_2") (pintype "passive"))
      (node (ref "R19") (pin "1") (pinfunction "1_1") (pintype "passive"))
    )
    (net (code "49") (name "Net-(Q7-B)") (class "Default")
      (node (ref "Q7") (pin "2") (pinfunction "B_2") (pintype "passive"))
      (node (ref "R17") (pin "2") (pinfunction "2_2") (pintype "passive"))
      (node (ref "R20") (pin "1") (pinfunction "1_1") (pintype "passive"))
    )
    (net (code "50") (name "Net-(Q8-B)") (class "Default")
      (node (ref "Q8") (pin "2") (pinfunction "B_2") (pintype "passive"))
      (node (ref "R26") (pin "1") (pinfunction "1_1") (pintype "passive"))
      (node (ref "R27") (pin "1") (pinfunction "1_1") (pintype "passive"))
    )
    (net (code "51") (name "Net-(Q8-C)") (class "Default")
      (node (ref "Q8") (pin "3") (pinfunction "C_3") (pintype "passive"))
      (node (ref "R21") (pin "2") (pinfunction "2_2") (pintype "passive"))
    )
    (net (code "52") (name "Net-(Q9-B)") (class "Default")
      (node (ref "Q9") (pin "2") (pinfunction "B_2") (pintype "passive"))
      (node (ref "R28") (pin "1") (pinfunction "1_1") (pintype "passive"))
      (node (ref "R29") (pin "1") (pinfunction "1_1") (pintype "passive"))
    )
    (net (code "53") (name "Net-(Q9-C)") (class "Default")
      (node (ref "Q9") (pin "3") (pinfunction "C_3") (pintype "passive"))
      (node (ref "R30") (pin "2") (pinfunction "2_2") (pintype "passive"))
    )
    (net (code "54") (name "Net-(Q10-B)") (class "Default")
      (node (ref "Q10") (pin "2") (pinfunction "B_2") (pintype "passive"))
      (node (ref "R31") (pin "2") (pinfunction "2_2") (pintype "passive"))
      (node (ref "R32") (pin "1") (pinfunction "1_1") (pintype "passive"))
    )
    (net (code "55") (name "Net-(Q11-B)") (class "Default")
      (node (ref "Q11") (pin "2") (pinfunction "B_2") (pintype "passive"))
      (node (ref "R37") (pin "1") (pinfunction "1_1") (pintype "passive"))
      (node (ref "R39") (pin "1") (pinfunction "1_1") (pintype "passive"))
    )
    (net (code "56") (name "Net-(Q11-C)") (class "Default")
      (node (ref "Q11") (pin "3") (pinfunction "C_3") (pintype "passive"))
      (node (ref "R33") (pin "1") (pinfunction "1_1") (pintype "passive"))
    )
    (net (code "57") (name "Net-(Q12-B)") (class "Default")
      (node (ref "Q12") (pin "2") (pinfunction "B_2") (pintype "passive"))
      (node (ref "R38") (pin "1") (pinfunction "1_1") (pintype "passive"))
      (node (ref "R42") (pin "1") (pinfunction "1_1") (pintype "passive"))
    )
    (net (code "58") (name "Net-(Q12-C)") (class "Default")
      (node (ref "Q12") (pin "3") (pinfunction "C_3") (pintype "passive"))
      (node (ref "R34") (pin "2") (pinfunction "2_2") (pintype "passive"))
    )
    (net (code "59") (name "Net-(Q13-B)") (class "Default")
      (node (ref "Q13") (pin "2") (pinfunction "B_2") (pintype "passive"))
      (node (ref "R40") (pin "1") (pinfunction "1_1") (pintype "passive"))
      (node (ref "R47") (pin "1") (pinfunction "1_1") (pintype "passive"))
    )
    (net (code "60") (name "Net-(Q13-C)") (class "Default")
      (node (ref "Q13") (pin "3") (pinfunction "C_3") (pintype "passive"))
      (node (ref "R35") (pin "1") (pinfunction "1_1") (pintype "passive"))
    )
    (net (code "61") (name "Net-(Q14-B)") (class "Default")
      (node (ref "Q14") (pin "2") (pinfunction "B_2") (pintype "passive"))
      (node (ref "R41") (pin "1") (pinfunction "1_1") (pintype "passive"))
      (node (ref "R48") (pin "1") (pinfunction "1_1") (pintype "passive"))
    )
    (net (code "62") (name "Net-(Q14-C)") (class "Default")
      (node (ref "Q14") (pin "3") (pinfunction "C_3") (pintype "passive"))
      (node (ref "R36") (pin "2") (pinfunction "2_2") (pintype "passive"))
    )
    (net (code "63") (name "Net-(Q15-B)") (class "Default")
      (node (ref "Q15") (pin "2") (pinfunction "B_2") (pintype "passive"))
      (node (ref "R49") (pin "2") (pinfunction "2_2") (pintype "passive"))
      (node (ref "R53") (pin "1") (pinfunction "1_1") (pintype "passive"))
    )
    (net (code "64") (name "Net-(Q15-C)") (class "Default")
      (node (ref "Q15") (pin "3") (pinfunction "C_3") (pintype "passive"))
      (node (ref "R43") (pin "2") (pinfunction "2_2") (pintype "passive"))
    )
    (net (code "65") (name "Net-(Q16-B)") (class "Default")
      (node (ref "Q16") (pin "2") (pinfunction "B_2") (pintype "passive"))
      (node (ref "R50") (pin "2") (pinfunction "2_2") (pintype "passive"))
      (node (ref "R54") (pin "1") (pinfunction "1_1") (pintype "passive"))
    )
    (net (code "66") (name "Net-(Q16-C)") (class "Default")
      (node (ref "Q16") (pin "3") (pinfunction "C_3") (pintype "passive"))
      (node (ref "R44") (pin "2") (pinfunction "2_2") (pintype "passive"))
    )
    (net (code "67") (name "Net-(Q17-B)") (class "Default")
      (node (ref "Q17") (pin "2") (pinfunction "B_2") (pintype "passive"))
      (node (ref "R51") (pin "2") (pinfunction "2_2") (pintype "passive"))
      (node (ref "R55") (pin "1") (pinfunction "1_1") (pintype "passive"))
    )
    (net (code "68") (name "Net-(Q17-C)") (class "Default")
      (node (ref "Q17") (pin "3") (pinfunction "C_3") (pintype "passive"))
      (node (ref "R45") (pin "2") (pinfunction "2_2") (pintype "passive"))
    )
    (net (code "69") (name "Net-(Q18-B)") (class "Default")
      (node (ref "Q18") (pin "2") (pinfunction "B_2") (pintype "passive"))
      (node (ref "R52") (pin "2") (pinfunction "2_2") (pintype "passive"))
      (node (ref "R56") (pin "1") (pinfunction "1_1") (pintype "passive"))
    )
    (net (code "70") (name "Net-(Q18-C)") (class "Default")
      (node (ref "Q18") (pin "3") (pinfunction "C_3") (pintype "passive"))
      (node (ref "R46") (pin "2") (pinfunction "2_2") (pintype "passive"))
    )
    (net (code "71") (name "ONEWIRE") (class "Default")
      (node (ref "P4") (pin "6") (pinfunction "6_6") (pintype "passive"))
      (node (ref "R59") (pin "1") (pinfunction "1_1") (pintype "passive"))
      (node (ref "TS1") (pin "2") (pinfunction "DQ_2") (pintype "passive"))
    )
    (net (code "72") (name "PB1") (class "Default")
      (node (ref "C4") (pin "2") (pinfunction "2_2") (pintype "passive"))
      (node (ref "P3") (pin "1") (pinfunction "1_1") (pintype "passive"))
      (node (ref "PB1") (pin "1") (pinfunction "1_1") (pintype "passive"))
      (node (ref "R22") (pin "1") (pinfunction "1_1") (pintype "passive"))
    )
    (net (code "73") (name "PB2") (class "Default")
      (node (ref "C5") (pin "2") (pinfunction "2_2") (pintype "passive"))
      (node (ref "P3") (pin "3") (pinfunction "3_3") (pintype "passive"))
      (node (ref "PB2") (pin "1") (pinfunction "1_1") (pintype "passive"))
      (node (ref "R23") (pin "1") (pinfunction "1_1") (pintype "passive"))
    )
    (net (code "74") (name "PB3") (class "Default")
      (node (ref "C6") (pin "2") (pinfunction "2_2") (pintype "passive"))
      (node (ref "P3") (pin "5") (pinfunction "5_5") (pintype "passive"))
      (node (ref "PB3") (pin "1") (pinfunction "1_1") (pintype "passive"))
      (node (ref "R24") (pin "1") (pinfunction "1_1") (pintype "passive"))
    )
    (net (code "75") (name "PB4") (class "Default")
      (node (ref "C7") (pin "2") (pinfunction "2_2") (pintype "passive"))
      (node (ref "P3") (pin "7") (pinfunction "7_7") (pintype "passive"))
      (node (ref "PB4") (pin "1") (pinfunction "1_1") (pintype "passive"))
      (node (ref "R25") (pin "1") (pinfunction "1_1") (pintype "passive"))
    )
    (net (code "76") (name "VCC") (class "Default")
      (node (ref "C10") (pin "1") (pinfunction "1_1") (pintype "passive"))
      (node (ref "D1") (pin "1") (pinfunction "A_1") (pintype "passive"))
      (node (ref "D2") (pin "1") (pinfunction "A_1") (pintype "passive"))
      (node (ref "D3") (pin "1") (pinfunction "A_1") (pintype "passive"))
      (node (ref "D4") (pin "1") (pinfunction "A_1") (pintype "passive"))
      (node (ref "P1") (pin "2") (pinfunction "2_2") (pintype "passive"))
      (node (ref "Q1") (pin "1") (pinfunction "E_1") (pintype "passive"))
      (node (ref "Q10") (pin "1") (pinfunction "E_1") (pintype "passive"))
      (node (ref "Q4") (pin "1") (pinfunction "E_1") (pintype "passive"))
      (node (ref "Q6") (pin "1") (pinfunction "E_1") (pintype "passive"))
      (node (ref "Q7") (pin "1") (pinfunction "E_1") (pintype "passive"))
      (node (ref "R1") (pin "1") (pinfunction "1_1") (pintype "passive"))
      (node (ref "R10") (pin "1") (pinfunction "1_1") (pintype "passive"))
      (node (ref "R16") (pin "1") (pinfunction "1_1") (pintype "passive"))
      (node (ref "R17") (pin "1") (pinfunction "1_1") (pintype "passive"))
      (node (ref "R22") (pin "2") (pinfunction "2_2") (pintype "passive"))
      (node (ref "R23") (pin "2") (pinfunction "2_2") (pintype "passive"))
      (node (ref "R24") (pin "2") (pinfunction "2_2") (pintype "passive"))
      (node (ref "R25") (pin "2") (pinfunction "2_2") (pintype "passive"))
      (node (ref "R31") (pin "1") (pinfunction "1_1") (pintype "passive"))
      (node (ref "R57") (pin "2") (pinfunction "2_2") (pintype "passive"))
      (node (ref "R58") (pin "2") (pinfunction "2_2") (pintype "passive"))
      (node (ref "R59") (pin "2") (pinfunction "2_2") (pintype "passive"))
      (node (ref "R6") (pin "2") (pinfunction "2_2") (pintype "passive"))
      (node (ref "R7") (pin "2") (pinfunction "2_2") (pintype "passive"))
      (node (ref "R8") (pin "2") (pinfunction "2_2") (pintype "passive"))
      (node (ref "RP2") (pin "1") (pinfunction "A_1") (pintype "passive"))
      (node (ref "TS1") (pin "3") (pinfunction "VDD_3") (pintype "passive"))
    )
  )
)
